# QCLogic_Rev_A_Sht4_QSPI_Flash.net
KiCad netlist of a schematic drawn in Altium Designer
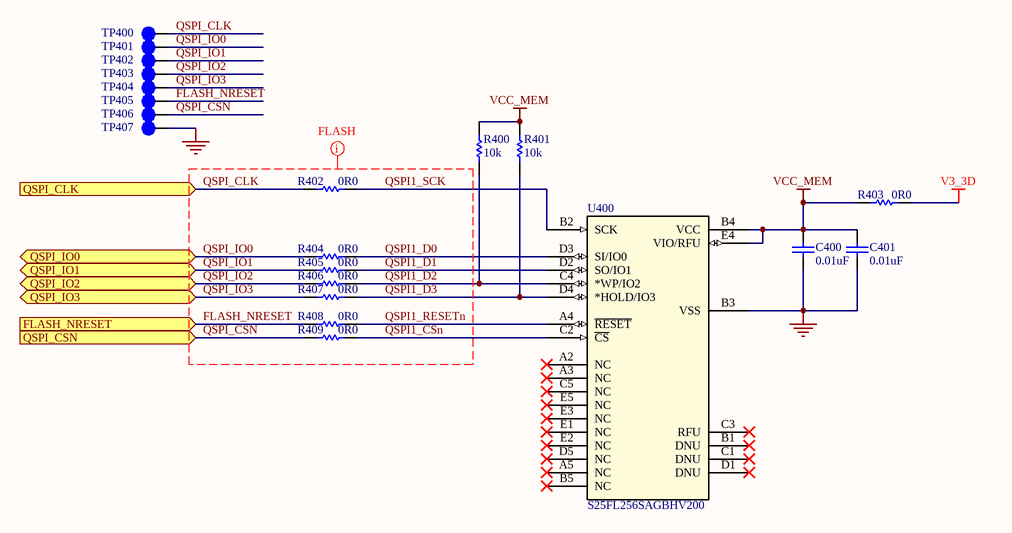
[diagram p0: QCLogic Rev A Sht4 QSPI Flash.SchDoc]

(export (version "E")
  (design (tool "Eeschema 10.0.6"))
  (components
    (comp (ref "C400")
      (value "0.01uF")
      (footprint "SMD CAP 0402")
      (description "CAP CER 10000PF 16V X7R 0402")
      (fields (field (name "2. MANUFACTURER PART NUMBER") "0402B103K160CT"))
      (libsource (lib "SBCLib") (part "CAP MLCC SMD"))
    )
    (comp (ref "C401")
      (value "0.01uF")
      (footprint "SMD CAP 0402")
      (description "CAP CER 10000PF 16V X7R 0402")
      (fields (field (name "2. MANUFACTURER PART NUMBER") "0402B103K160CT"))
      (libsource (lib "SBCLib") (part "CAP MLCC SMD"))
    )
    (comp (ref "R400")
      (value "10k")
      (footprint "SMD RES 0402")
      (description "RES SMD 10K OHM 1% 1/16W 0402")
      (fields (field (name "2. MANUFACTURER PART NUMBER") "RC0402FR-0710KL"))
      (libsource (lib "SBCLib") (part "RES SMD"))
    )
    (comp (ref "R401")
      (value "10k")
      (footprint "SMD RES 0402")
      (description "RES SMD 10K OHM 1% 1/16W 0402")
      (fields (field (name "2. MANUFACTURER PART NUMBER") "RC0402FR-0710KL"))
      (libsource (lib "SBCLib") (part "RES SMD"))
    )
    (comp (ref "R402")
      (value "0R0")
      (footprint "SMD RES 0402")
      (description "RES SMD 0 OHM JUMPER 1/16W 0402")
      (fields (field (name "2. MANUFACTURER PART NUMBER") "RC0402FR-070RL"))
      (libsource (lib "SBCLib") (part "RES SMD"))
    )
    (comp (ref "R403")
      (value "0R0")
      (footprint "SMD RES 0402")
      (description "RES SMD 0 OHM JUMPER 1/16W 0402")
      (fields (field (name "2. MANUFACTURER PART NUMBER") "RC0402FR-070RL"))
      (libsource (lib "SBCLib") (part "RES SMD"))
    )
    (comp (ref "R404")
      (value "0R0")
      (footprint "SMD RES 0402")
      (description "RES SMD 0 OHM JUMPER 1/16W 0402")
      (fields (field (name "2. MANUFACTURER PART NUMBER") "RC0402FR-070RL"))
      (libsource (lib "SBCLib") (part "RES SMD"))
    )
    (comp (ref "R405")
      (value "0R0")
      (footprint "SMD RES 0402")
      (description "RES SMD 0 OHM JUMPER 1/16W 0402")
      (fields (field (name "2. MANUFACTURER PART NUMBER") "RC0402FR-070RL"))
      (libsource (lib "SBCLib") (part "RES SMD"))
    )
    (comp (ref "R406")
      (value "0R0")
      (footprint "SMD RES 0402")
      (description "RES SMD 0 OHM JUMPER 1/16W 0402")
      (fields (field (name "2. MANUFACTURER PART NUMBER") "RC0402FR-070RL"))
      (libsource (lib "SBCLib") (part "RES SMD"))
    )
    (comp (ref "R407")
      (value "0R0")
      (footprint "SMD RES 0402")
      (description "RES SMD 0 OHM JUMPER 1/16W 0402")
      (fields (field (name "2. MANUFACTURER PART NUMBER") "RC0402FR-070RL"))
      (libsource (lib "SBCLib") (part "RES SMD"))
    )
    (comp (ref "R408")
      (value "0R0")
      (footprint "SMD RES 0402")
      (description "RES SMD 0 OHM JUMPER 1/16W 0402")
      (fields (field (name "2. MANUFACTURER PART NUMBER") "RC0402FR-070RL"))
      (libsource (lib "SBCLib") (part "RES SMD"))
    )
    (comp (ref "R409")
      (value "0R0")
      (footprint "SMD RES 0402")
      (description "RES SMD 0 OHM JUMPER 1/16W 0402")
      (fields (field (name "2. MANUFACTURER PART NUMBER") "RC0402FR-070RL"))
      (libsource (lib "SBCLib") (part "RES SMD"))
    )
    (comp (ref "TP400")
      (value "TESTPOINT SMD")
      (footprint "TESTPOINT 0.5mm DIA")
      (description "TESTPOINT SMD PAD")
      (libsource (lib "SBCLib") (part "TESTPOINT PAD"))
    )
    (comp (ref "TP401")
      (value "TESTPOINT SMD")
      (footprint "TESTPOINT 0.5mm DIA")
      (description "TESTPOINT SMD PAD")
      (libsource (lib "SBCLib") (part "TESTPOINT PAD"))
    )
    (comp (ref "TP402")
      (value "TESTPOINT SMD")
      (footprint "TESTPOINT 0.5mm DIA")
      (description "TESTPOINT SMD PAD")
      (libsource (lib "SBCLib") (part "TESTPOINT PAD"))
    )
    (comp (ref "TP403")
      (value "TESTPOINT SMD")
      (footprint "TESTPOINT 0.5mm DIA")
      (description "TESTPOINT SMD PAD")
      (libsource (lib "SBCLib") (part "TESTPOINT PAD"))
    )
    (comp (ref "TP404")
      (value "TESTPOINT SMD")
      (footprint "TESTPOINT 0.5mm DIA")
      (description "TESTPOINT SMD PAD")
      (libsource (lib "SBCLib") (part "TESTPOINT PAD"))
    )
    (comp (ref "TP405")
      (value "TESTPOINT SMD")
      (footprint "TESTPOINT 0.5mm DIA")
      (description "TESTPOINT SMD PAD")
      (libsource (lib "SBCLib") (part "TESTPOINT PAD"))
    )
    (comp (ref "TP406")
      (value "TESTPOINT SMD")
      (footprint "TESTPOINT 0.5mm DIA")
      (description "TESTPOINT SMD PAD")
      (libsource (lib "SBCLib") (part "TESTPOINT PAD"))
    )
    (comp (ref "TP407")
      (value "TESTPOINT SMD")
      (footprint "TESTPOINT 0.5mm DIA")
      (description "TESTPOINT SMD PAD")
      (libsource (lib "SBCLib") (part "TESTPOINT PAD"))
    )
    (comp (ref "U400")
      (value "S25FL256SAGBHV200")
      (footprint "TFBGA-24 8x6")
      (description "IC FLASH 256M SPI 133MHZ 24BGA")
      (libsource (lib "SBCLib") (part "IC FLASH 256M SPI 133MHZ 24BGA"))
    )
  )
  (nets
    (net (code "1") (name "/FLASH_NRESET") (class "Default")
      (node (ref "R408") (pin "1") (pinfunction "1_1") (pintype "passive"))
      (node (ref "TP405") (pin "1") (pinfunction "1_1") (pintype "passive"))
    )
    (net (code "2") (name "/QSPI1_CSn") (class "Default")
      (node (ref "R409") (pin "2") (pinfunction "2_2") (pintype "passive"))
      (node (ref "U400") (pin "C2") (pinfunction "~{CS}_C2") (pintype "input"))
    )
    (net (code "3") (name "/QSPI1_D0") (class "Default")
      (node (ref "R404") (pin "2") (pinfunction "2_2") (pintype "passive"))
      (node (ref "U400") (pin "D3") (pinfunction "SI/IO0_D3") (pintype "bidirectional"))
    )
    (net (code "4") (name "/QSPI1_D1") (class "Default")
      (node (ref "R405") (pin "2") (pinfunction "2_2") (pintype "passive"))
      (node (ref "U400") (pin "D2") (pinfunction "SO/IO1_D2") (pintype "bidirectional"))
    )
    (net (code "5") (name "/QSPI1_D2") (class "Default")
      (node (ref "R400") (pin "2") (pinfunction "2_2") (pintype "passive"))
      (node (ref "R406") (pin "2") (pinfunction "2_2") (pintype "passive"))
      (node (ref "U400") (pin "C4") (pinfunction "*WP/IO2_C4") (pintype "bidirectional"))
    )
    (net (code "6") (name "/QSPI1_D3") (class "Default")
      (node (ref "R401") (pin "2") (pinfunction "2_2") (pintype "passive"))
      (node (ref "R407") (pin "2") (pinfunction "2_2") (pintype "passive"))
      (node (ref "U400") (pin "D4") (pinfunction "*HOLD/IO3_D4") (pintype "bidirectional"))
    )
    (net (code "7") (name "/QSPI1_RESETn") (class "Default")
      (node (ref "R408") (pin "2") (pinfunction "2_2") (pintype "passive"))
      (node (ref "U400") (pin "A4") (pinfunction "~{RESET}_A4") (pintype "bidirectional"))
    )
    (net (code "8") (name "/QSPI1_SCK") (class "Default")
      (node (ref "R402") (pin "2") (pinfunction "2_2") (pintype "passive"))
      (node (ref "U400") (pin "B2") (pinfunction "SCK_B2") (pintype "input"))
    )
    (net (code "9") (name "/QSPI_CLK") (class "Default")
      (node (ref "R402") (pin "1") (pinfunction "1_1") (pintype "passive"))
      (node (ref "TP400") (pin "1") (pinfunction "1_1") (pintype "passive"))
    )
    (net (code "10") (name "/QSPI_CSN") (class "Default")
      (node (ref "R409") (pin "1") (pinfunction "1_1") (pintype "passive"))
      (node (ref "TP406") (pin "1") (pinfunction "1_1") (pintype "passive"))
    )
    (net (code "11") (name "/QSPI_IO0") (class "Default")
      (node (ref "R404") (pin "1") (pinfunction "1_1") (pintype "passive"))
      (node (ref "TP401") (pin "1") (pinfunction "1_1") (pintype "passive"))
    )
    (net (code "12") (name "/QSPI_IO1") (class "Default")
      (node (ref "R405") (pin "1") (pinfunction "1_1") (pintype "passive"))
      (node (ref "TP402") (pin "1") (pinfunction "1_1") (pintype "passive"))
    )
    (net (code "13") (name "/QSPI_IO2") (class "Default")
      (node (ref "R406") (pin "1") (pinfunction "1_1") (pintype "passive"))
      (node (ref "TP403") (pin "1") (pinfunction "1_1") (pintype "passive"))
    )
    (net (code "14") (name "/QSPI_IO3") (class "Default")
      (node (ref "R407") (pin "1") (pinfunction "1_1") (pintype "passive"))
      (node (ref "TP404") (pin "1") (pinfunction "1_1") (pintype "passive"))
    )
    (net (code "15") (name "GND") (class "Default")
      (node (ref "C400") (pin "2") (pinfunction "2_2") (pintype "passive"))
      (node (ref "C401") (pin "2") (pinfunction "2_2") (pintype "passive"))
      (node (ref "TP407") (pin "1") (pinfunction "1_1") (pintype "passive"))
      (node (ref "U400") (pin "B3") (pinfunction "VSS_B3") (pintype "power_in"))
    )
    (net (code "16") (name "V3_3D") (class "Default")
      (node (ref "R403") (pin "2") (pinfunction "2_2") (pintype "passive"))
    )
    (net (code "17") (name "VCC_MEM") (class "Default")
      (node (ref "C400") (pin "1") (pinfunction "1_1") (pintype "passive"))
      (node (ref "C401") (pin "1") (pinfunction "1_1") (pintype "passive"))
      (node (ref "R400") (pin "1") (pinfunction "1_1") (pintype "passive"))
      (node (ref "R401") (pin "1") (pinfunction "1_1") (pintype "passive"))
      (node (ref "R403") (pin "1") (pinfunction "1_1") (pintype "passive"))
      (node (ref "U400") (pin "B4") (pinfunction "VCC_B4") (pintype "power_in"))
      (node (ref "U400") (pin "E4") (pinfunction "VIO/RFU_E4") (pintype "bidirectional"))
    )
    (net (code "18") (name "unconnected-(U400-DNU-PadB1)") (class "Default")
      (node (ref "U400") (pin "B1") (pinfunction "DNU_B1") (pintype "passive+no_connect"))
    )
    (net (code "19") (name "unconnected-(U400-DNU-PadC1)") (class "Default")
      (node (ref "U400") (pin "C1") (pinfunction "DNU_C1") (pintype "passive+no_connect"))
    )
    (net (code "20") (name "unconnected-(U400-DNU-PadD1)") (class "Default")
      (node (ref "U400") (pin "D1") (pinfunction "DNU_D1") (pintype "passive+no_connect"))
    )
    (net (code "21") (name "unconnected-(U400-NC-PadA2)") (class "Default")
      (node (ref "U400") (pin "A2") (pinfunction "NC_A2") (pintype "passive+no_connect"))
    )
    (net (code "22") (name "unconnected-(U400-NC-PadA3)") (class "Default")
      (node (ref "U400") (pin "A3") (pinfunction "NC_A3") (pintype "passive+no_connect"))
    )
    (net (code "23") (name "unconnected-(U400-NC-PadA5)") (class "Default")
      (node (ref "U400") (pin "A5") (pinfunction "NC_A5") (pintype "passive+no_connect"))
    )
    (net (code "24") (name "unconnected-(U400-NC-PadB5)") (class "Default")
      (node (ref "U400") (pin "B5") (pinfunction "NC_B5") (pintype "passive+no_connect"))
    )
    (net (code "25") (name "unconnected-(U400-NC-PadC5)") (class "Default")
      (node (ref "U400") (pin "C5") (pinfunction "NC_C5") (pintype "passive+no_connect"))
    )
    (net (code "26") (name "unconnected-(U400-NC-PadD5)") (class "Default")
      (node (ref "U400") (pin "D5") (pinfunction "NC_D5") (pintype "passive+no_connect"))
    )
    (net (code "27") (name "unconnected-(U400-NC-PadE1)") (class "Default")
      (node (ref "U400") (pin "E1") (pinfunction "NC_E1") (pintype "passive+no_connect"))
    )
    (net (code "28") (name "unconnected-(U400-NC-PadE2)") (class "Default")
      (node (ref "U400") (pin "E2") (pinfunction "NC_E2") (pintype "passive+no_connect"))
    )
    (net (code "29") (name "unconnected-(U400-NC-PadE3)") (class "Default")
      (node (ref "U400") (pin "E3") (pinfunction "NC_E3") (pintype "passive+no_connect"))
    )
    (net (code "30") (name "unconnected-(U400-NC-PadE5)") (class "Default")
      (node (ref "U400") (pin "E5") (pinfunction "NC_E5") (pintype "passive+no_connect"))
    )
    (net (code "31") (name "unconnected-(U400-RFU-PadC3)") (class "Default")
      (node (ref "U400") (pin "C3") (pinfunction "RFU_C3") (pintype "passive+no_connect"))
    )
  )
)
